# US_Sensor-board.net
KiCad netlist of a schematic drawn in Altium Designer
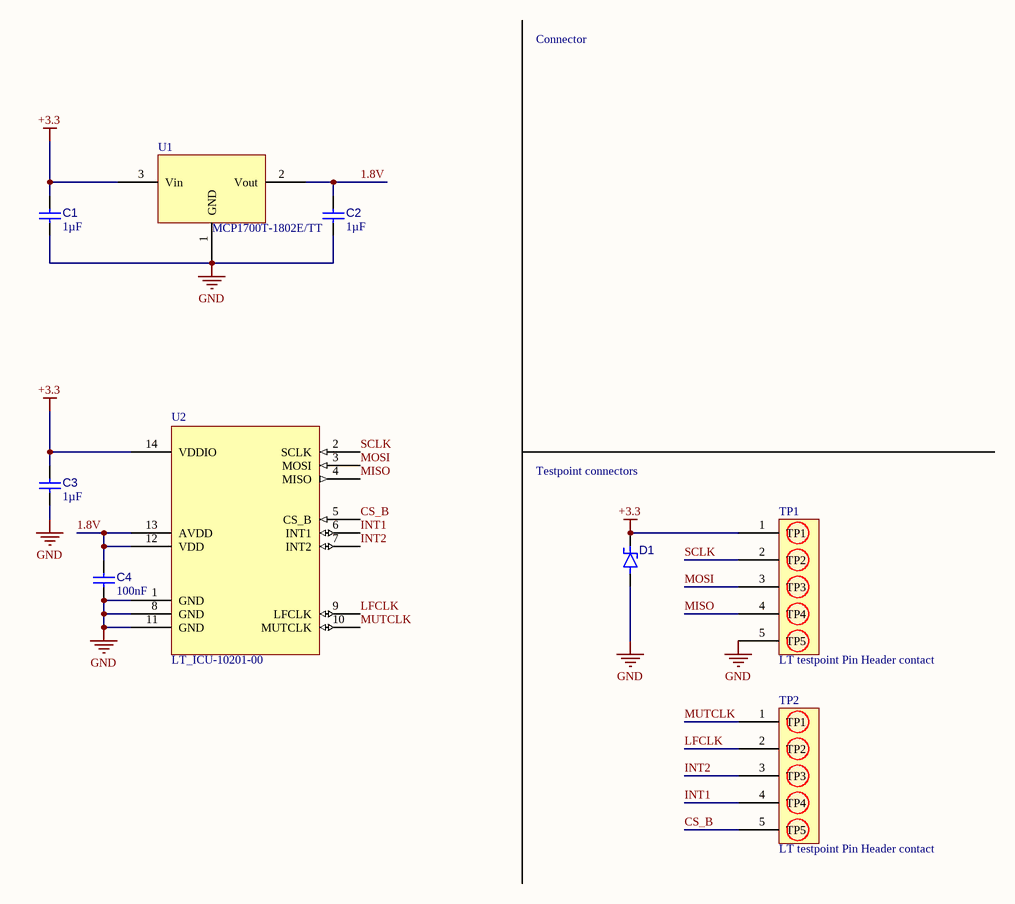
[diagram p0: US_Sensor-board.SchDoc]

(export (version "E")
  (design (tool "Eeschema 10.0.6"))
  (components
    (comp (ref "C1")
      (value "1µF")
      (footprint "LT_Capacitor_1uF-Footprint-1")
      (description "SMD Multilayer Ceramic Capacitor, 1 µF, 6.3 V, 0603 [1608 Metric], ± 10%, X7R")
      (fields (field (name "Comment") "1uF"))
      (libsource (lib "Riistvara Projekt") (part "1uF"))
    )
    (comp (ref "C2")
      (value "1µF")
      (footprint "LT_Capacitor_1uF-Footprint-1")
      (description "SMD Multilayer Ceramic Capacitor, 1 µF, 6.3 V, 0603 [1608 Metric], ± 10%, X7R")
      (fields (field (name "Comment") "1uF"))
      (libsource (lib "Riistvara Projekt") (part "1uF"))
    )
    (comp (ref "C3")
      (value "1µF")
      (footprint "LT_Capacitor_1uF-Footprint-1")
      (description "SMD Multilayer Ceramic Capacitor, 1 µF, 6.3 V, 0603 [1608 Metric], ± 10%, X7R")
      (fields (field (name "Comment") "1uF"))
      (libsource (lib "Riistvara Projekt") (part "1uF"))
    )
    (comp (ref "C4")
      (value "100nF")
      (footprint "CAPC1608X08N")
      (description "SMD Multilayer Ceramic Capacitor, 0.1 µF, 25 V, 0603 [1608 Metric], ± 10%, X7R")
      (libsource (lib "Riistvara Projekt") (part "100nF"))
    )
    (comp (ref "D1")
      (value "MM3Z9V1B - RVP")
      (footprint "SOD323-F - RVP")
      (description "Zener Single Diode, 9.1 V, 200 mW, SOD-323F, 2 Pins, 150 °C, Surface Mount")
      (libsource (lib "Riistvara Projekt") (part "DIODE-2"))
    )
    (comp (ref "TP1")
      (value "LT testpoint Pin Header contact")
      (footprint "New footprint 1")
      (description "5 pin testpoint contact")
      (libsource (lib "Riistvara Projekt") (part "TestPointContact"))
    )
    (comp (ref "TP2")
      (value "LT testpoint Pin Header contact")
      (footprint "New footprint 1")
      (description "5 pin testpoint contact")
      (libsource (lib "Riistvara Projekt") (part "TestPointContact"))
    )
    (comp (ref "U1")
      (value "MCP1700T-1802E/TT")
      (footprint "MCP1700T-1802E/TT")
      (description "Fixed LDO Voltage Regulator, 2.3V to 6V, 178mV Dropout, 1.8Vout, 200mAout, SOT-23-3")
      (libsource (lib "Riistvara Projekt") (part "LT_Voltage regulator LDO 1.8V"))
    )
    (comp (ref "U2")
      (value "LT_ICU-10201-00")
      (footprint "LT_ICU-10201-00-Footprint-1")
      (description "High-performance, miniature, ultra-low power, long-range ultrasonic transceiver.")
      (libsource (lib "Riistvara Projekt") (part "ICU-10201"))
    )
  )
  (nets
    (net (code "1") (name "+3.3") (class "Default")
      (node (ref "C1") (pin "2") (pinfunction "2_2") (pintype "passive"))
      (node (ref "C3") (pin "2") (pinfunction "2_2") (pintype "passive"))
      (node (ref "D1") (pin "1") (pinfunction "K_1") (pintype "passive"))
      (node (ref "TP1") (pin "1") (pinfunction "TP1_1") (pintype "passive"))
      (node (ref "U1") (pin "3") (pinfunction "Vin_3") (pintype "passive"))
      (node (ref "U2") (pin "14") (pinfunction "VDDIO_14") (pintype "power_in"))
    )
    (net (code "2") (name "/1.8V") (class "Default")
      (node (ref "C2") (pin "2") (pinfunction "2_2") (pintype "passive"))
      (node (ref "C4") (pin "2") (pinfunction "2_2") (pintype "passive"))
      (node (ref "U1") (pin "2") (pinfunction "Vout_2") (pintype "passive"))
      (node (ref "U2") (pin "12") (pinfunction "VDD_12") (pintype "power_in"))
      (node (ref "U2") (pin "13") (pinfunction "AVDD_13") (pintype "power_in"))
    )
    (net (code "3") (name "/CS_B") (class "Default")
      (node (ref "TP2") (pin "5") (pinfunction "TP5_5") (pintype "passive"))
      (node (ref "U2") (pin "5") (pinfunction "CS_B_5") (pintype "input"))
    )
    (net (code "4") (name "/INT1") (class "Default")
      (node (ref "TP2") (pin "4") (pinfunction "TP4_4") (pintype "passive"))
      (node (ref "U2") (pin "6") (pinfunction "INT1_6") (pintype "bidirectional"))
    )
    (net (code "5") (name "/INT2") (class "Default")
      (node (ref "TP2") (pin "3") (pinfunction "TP3_3") (pintype "passive"))
      (node (ref "U2") (pin "7") (pinfunction "INT2_7") (pintype "bidirectional"))
    )
    (net (code "6") (name "/LFCLK") (class "Default")
      (node (ref "TP2") (pin "2") (pinfunction "TP2_2") (pintype "passive"))
      (node (ref "U2") (pin "9") (pinfunction "LFCLK_9") (pintype "bidirectional"))
    )
    (net (code "7") (name "/MISO") (class "Default")
      (node (ref "TP1") (pin "4") (pinfunction "TP4_4") (pintype "passive"))
      (node (ref "U2") (pin "4") (pinfunction "MISO_4") (pintype "output"))
    )
    (net (code "8") (name "/MOSI") (class "Default")
      (node (ref "TP1") (pin "3") (pinfunction "TP3_3") (pintype "passive"))
      (node (ref "U2") (pin "3") (pinfunction "MOSI_3") (pintype "input"))
    )
    (net (code "9") (name "/MUTCLK") (class "Default")
      (node (ref "TP2") (pin "1") (pinfunction "TP1_1") (pintype "passive"))
      (node (ref "U2") (pin "10") (pinfunction "MUTCLK_10") (pintype "bidirectional"))
    )
    (net (code "10") (name "/SCLK") (class "Default")
      (node (ref "TP1") (pin "2") (pinfunction "TP2_2") (pintype "passive"))
      (node (ref "U2") (pin "2") (pinfunction "SCLK_2") (pintype "input"))
    )
    (net (code "11") (name "GND") (class "Default")
      (node (ref "C1") (pin "1") (pinfunction "1_1") (pintype "passive"))
      (node (ref "C2") (pin "1") (pinfunction "1_1") (pintype "passive"))
      (node (ref "C3") (pin "1") (pinfunction "1_1") (pintype "passive"))
      (node (ref "C4") (pin "1") (pinfunction "1_1") (pintype "passive"))
      (node (ref "D1") (pin "2") (pinfunction "A_2") (pintype "passive"))
      (node (ref "TP1") (pin "5") (pinfunction "TP5_5") (pintype "passive"))
      (node (ref "U1") (pin "1") (pinfunction "GND_1") (pintype "passive"))
      (node (ref "U2") (pin "1") (pinfunction "GND_1") (pintype "power_in"))
      (node (ref "U2") (pin "11") (pinfunction "GND_11") (pintype "power_in"))
      (node (ref "U2") (pin "8") (pinfunction "GND_8") (pintype "power_in"))
    )
  )
)
